# Schematic.net
KiCad netlist of a schematic drawn in EAGLE
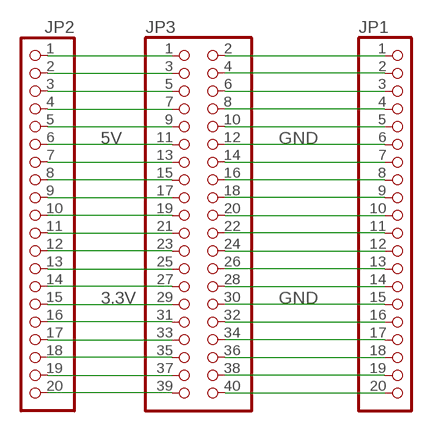
[diagram p0: schematic, sheet 1]

(export (version "E")
  (design (tool "Eeschema 10.0.6"))
  (components
    (comp (ref "JP1")
      (value "PINHD-1X20")
      (footprint "eagle-import:1X20")
      (libsource (lib "eagle-import") (part "PINHD-1X20"))
    )
    (comp (ref "JP2")
      (value "PINHD-1X20")
      (footprint "eagle-import:1X20")
      (libsource (lib "eagle-import") (part "PINHD-1X20"))
    )
    (comp (ref "JP3")
      (value "PINHD-2X20")
      (footprint "eagle-import:2X20")
      (libsource (lib "eagle-import") (part "PINHD-2X20"))
    )
  )
  (nets
    (net (code "1") (name "/3.3V") (class "Default")
      (node (ref "JP2") (pin "15") (pinfunction "15_15") (pintype "passive"))
      (node (ref "JP3") (pin "29") (pinfunction "29_29") (pintype "passive"))
    )
    (net (code "2") (name "/5V") (class "Default")
      (node (ref "JP2") (pin "6") (pinfunction "6_6") (pintype "passive"))
      (node (ref "JP3") (pin "11") (pinfunction "11_11") (pintype "passive"))
    )
    (net (code "3") (name "/GND") (class "Default")
      (node (ref "JP1") (pin "15") (pinfunction "15_15") (pintype "passive"))
      (node (ref "JP1") (pin "6") (pinfunction "6_6") (pintype "passive"))
      (node (ref "JP3") (pin "12") (pinfunction "12_12") (pintype "passive"))
      (node (ref "JP3") (pin "30") (pinfunction "30_30") (pintype "passive"))
    )
    (net (code "4") (name "Net-(JP1-Pad1)") (class "Default")
      (node (ref "JP1") (pin "1") (pinfunction "1_1") (pintype "passive"))
      (node (ref "JP3") (pin "2") (pinfunction "2_2") (pintype "passive"))
    )
    (net (code "5") (name "Net-(JP1-Pad2)") (class "Default")
      (node (ref "JP1") (pin "2") (pinfunction "2_2") (pintype "passive"))
      (node (ref "JP3") (pin "4") (pinfunction "4_4") (pintype "passive"))
    )
    (net (code "6") (name "Net-(JP1-Pad3)") (class "Default")
      (node (ref "JP1") (pin "3") (pinfunction "3_3") (pintype "passive"))
      (node (ref "JP3") (pin "6") (pinfunction "6_6") (pintype "passive"))
    )
    (net (code "7") (name "Net-(JP1-Pad4)") (class "Default")
      (node (ref "JP1") (pin "4") (pinfunction "4_4") (pintype "passive"))
      (node (ref "JP3") (pin "8") (pinfunction "8_8") (pintype "passive"))
    )
    (net (code "8") (name "Net-(JP1-Pad5)") (class "Default")
      (node (ref "JP1") (pin "5") (pinfunction "5_5") (pintype "passive"))
      (node (ref "JP3") (pin "10") (pinfunction "10_10") (pintype "passive"))
    )
    (net (code "9") (name "Net-(JP1-Pad7)") (class "Default")
      (node (ref "JP1") (pin "7") (pinfunction "7_7") (pintype "passive"))
      (node (ref "JP3") (pin "14") (pinfunction "14_14") (pintype "passive"))
    )
    (net (code "10") (name "Net-(JP1-Pad8)") (class "Default")
      (node (ref "JP1") (pin "8") (pinfunction "8_8") (pintype "passive"))
      (node (ref "JP3") (pin "16") (pinfunction "16_16") (pintype "passive"))
    )
    (net (code "11") (name "Net-(JP1-Pad9)") (class "Default")
      (node (ref "JP1") (pin "9") (pinfunction "9_9") (pintype "passive"))
      (node (ref "JP3") (pin "18") (pinfunction "18_18") (pintype "passive"))
    )
    (net (code "12") (name "Net-(JP1-Pad10)") (class "Default")
      (node (ref "JP1") (pin "10") (pinfunction "10_10") (pintype "passive"))
      (node (ref "JP3") (pin "20") (pinfunction "20_20") (pintype "passive"))
    )
    (net (code "13") (name "Net-(JP1-Pad11)") (class "Default")
      (node (ref "JP1") (pin "11") (pinfunction "11_11") (pintype "passive"))
      (node (ref "JP3") (pin "22") (pinfunction "22_22") (pintype "passive"))
    )
    (net (code "14") (name "Net-(JP1-Pad12)") (class "Default")
      (node (ref "JP1") (pin "12") (pinfunction "12_12") (pintype "passive"))
      (node (ref "JP3") (pin "24") (pinfunction "24_24") (pintype "passive"))
    )
    (net (code "15") (name "Net-(JP1-Pad13)") (class "Default")
      (node (ref "JP1") (pin "13") (pinfunction "13_13") (pintype "passive"))
      (node (ref "JP3") (pin "26") (pinfunction "26_26") (pintype "passive"))
    )
    (net (code "16") (name "Net-(JP1-Pad14)") (class "Default")
      (node (ref "JP1") (pin "14") (pinfunction "14_14") (pintype "passive"))
      (node (ref "JP3") (pin "28") (pinfunction "28_28") (pintype "passive"))
    )
    (net (code "17") (name "Net-(JP1-Pad16)") (class "Default")
      (node (ref "JP1") (pin "16") (pinfunction "16_16") (pintype "passive"))
      (node (ref "JP3") (pin "32") (pinfunction "32_32") (pintype "passive"))
    )
    (net (code "18") (name "Net-(JP1-Pad17)") (class "Default")
      (node (ref "JP1") (pin "17") (pinfunction "17_17") (pintype "passive"))
      (node (ref "JP3") (pin "34") (pinfunction "34_34") (pintype "passive"))
    )
    (net (code "19") (name "Net-(JP1-Pad18)") (class "Default")
      (node (ref "JP1") (pin "18") (pinfunction "18_18") (pintype "passive"))
      (node (ref "JP3") (pin "36") (pinfunction "36_36") (pintype "passive"))
    )
    (net (code "20") (name "Net-(JP1-Pad19)") (class "Default")
      (node (ref "JP1") (pin "19") (pinfunction "19_19") (pintype "passive"))
      (node (ref "JP3") (pin "38") (pinfunction "38_38") (pintype "passive"))
    )
    (net (code "21") (name "Net-(JP1-Pad20)") (class "Default")
      (node (ref "JP1") (pin "20") (pinfunction "20_20") (pintype "passive"))
      (node (ref "JP3") (pin "40") (pinfunction "40_40") (pintype "passive"))
    )
    (net (code "22") (name "Net-(JP2-Pad1)") (class "Default")
      (node (ref "JP2") (pin "1") (pinfunction "1_1") (pintype "passive"))
      (node (ref "JP3") (pin "1") (pinfunction "1_1") (pintype "passive"))
    )
    (net (code "23") (name "Net-(JP2-Pad2)") (class "Default")
      (node (ref "JP2") (pin "2") (pinfunction "2_2") (pintype "passive"))
      (node (ref "JP3") (pin "3") (pinfunction "3_3") (pintype "passive"))
    )
    (net (code "24") (name "Net-(JP2-Pad3)") (class "Default")
      (node (ref "JP2") (pin "3") (pinfunction "3_3") (pintype "passive"))
      (node (ref "JP3") (pin "5") (pinfunction "5_5") (pintype "passive"))
    )
    (net (code "25") (name "Net-(JP2-Pad4)") (class "Default")
      (node (ref "JP2") (pin "4") (pinfunction "4_4") (pintype "passive"))
      (node (ref "JP3") (pin "7") (pinfunction "7_7") (pintype "passive"))
    )
    (net (code "26") (name "Net-(JP2-Pad5)") (class "Default")
      (node (ref "JP2") (pin "5") (pinfunction "5_5") (pintype "passive"))
      (node (ref "JP3") (pin "9") (pinfunction "9_9") (pintype "passive"))
    )
    (net (code "27") (name "Net-(JP2-Pad7)") (class "Default")
      (node (ref "JP2") (pin "7") (pinfunction "7_7") (pintype "passive"))
      (node (ref "JP3") (pin "13") (pinfunction "13_13") (pintype "passive"))
    )
    (net (code "28") (name "Net-(JP2-Pad8)") (class "Default")
      (node (ref "JP2") (pin "8") (pinfunction "8_8") (pintype "passive"))
      (node (ref "JP3") (pin "15") (pinfunction "15_15") (pintype "passive"))
    )
    (net (code "29") (name "Net-(JP2-Pad9)") (class "Default")
      (node (ref "JP2") (pin "9") (pinfunction "9_9") (pintype "passive"))
      (node (ref "JP3") (pin "17") (pinfunction "17_17") (pintype "passive"))
    )
    (net (code "30") (name "Net-(JP2-Pad10)") (class "Default")
      (node (ref "JP2") (pin "10") (pinfunction "10_10") (pintype "passive"))
      (node (ref "JP3") (pin "19") (pinfunction "19_19") (pintype "passive"))
    )
    (net (code "31") (name "Net-(JP2-Pad11)") (class "Default")
      (node (ref "JP2") (pin "11") (pinfunction "11_11") (pintype "passive"))
      (node (ref "JP3") (pin "21") (pinfunction "21_21") (pintype "passive"))
    )
    (net (code "32") (name "Net-(JP2-Pad12)") (class "Default")
      (node (ref "JP2") (pin "12") (pinfunction "12_12") (pintype "passive"))
      (node (ref "JP3") (pin "23") (pinfunction "23_23") (pintype "passive"))
    )
    (net (code "33") (name "Net-(JP2-Pad13)") (class "Default")
      (node (ref "JP2") (pin "13") (pinfunction "13_13") (pintype "passive"))
      (node (ref "JP3") (pin "25") (pinfunction "25_25") (pintype "passive"))
    )
    (net (code "34") (name "Net-(JP2-Pad14)") (class "Default")
      (node (ref "JP2") (pin "14") (pinfunction "14_14") (pintype "passive"))
      (node (ref "JP3") (pin "27") (pinfunction "27_27") (pintype "passive"))
    )
    (net (code "35") (name "Net-(JP2-Pad16)") (class "Default")
      (node (ref "JP2") (pin "16") (pinfunction "16_16") (pintype "passive"))
      (node (ref "JP3") (pin "31") (pinfunction "31_31") (pintype "passive"))
    )
    (net (code "36") (name "Net-(JP2-Pad17)") (class "Default")
      (node (ref "JP2") (pin "17") (pinfunction "17_17") (pintype "passive"))
      (node (ref "JP3") (pin "33") (pinfunction "33_33") (pintype "passive"))
    )
    (net (code "37") (name "Net-(JP2-Pad18)") (class "Default")
      (node (ref "JP2") (pin "18") (pinfunction "18_18") (pintype "passive"))
      (node (ref "JP3") (pin "35") (pinfunction "35_35") (pintype "passive"))
    )
    (net (code "38") (name "Net-(JP2-Pad19)") (class "Default")
      (node (ref "JP2") (pin "19") (pinfunction "19_19") (pintype "passive"))
      (node (ref "JP3") (pin "37") (pinfunction "37_37") (pintype "passive"))
    )
    (net (code "39") (name "Net-(JP2-Pad20)") (class "Default")
      (node (ref "JP2") (pin "20") (pinfunction "20_20") (pintype "passive"))
      (node (ref "JP3") (pin "39") (pinfunction "39_39") (pintype "passive"))
    )
  )
)
